# sct.net
KiCad netlist of a schematic drawn in EasyEDA
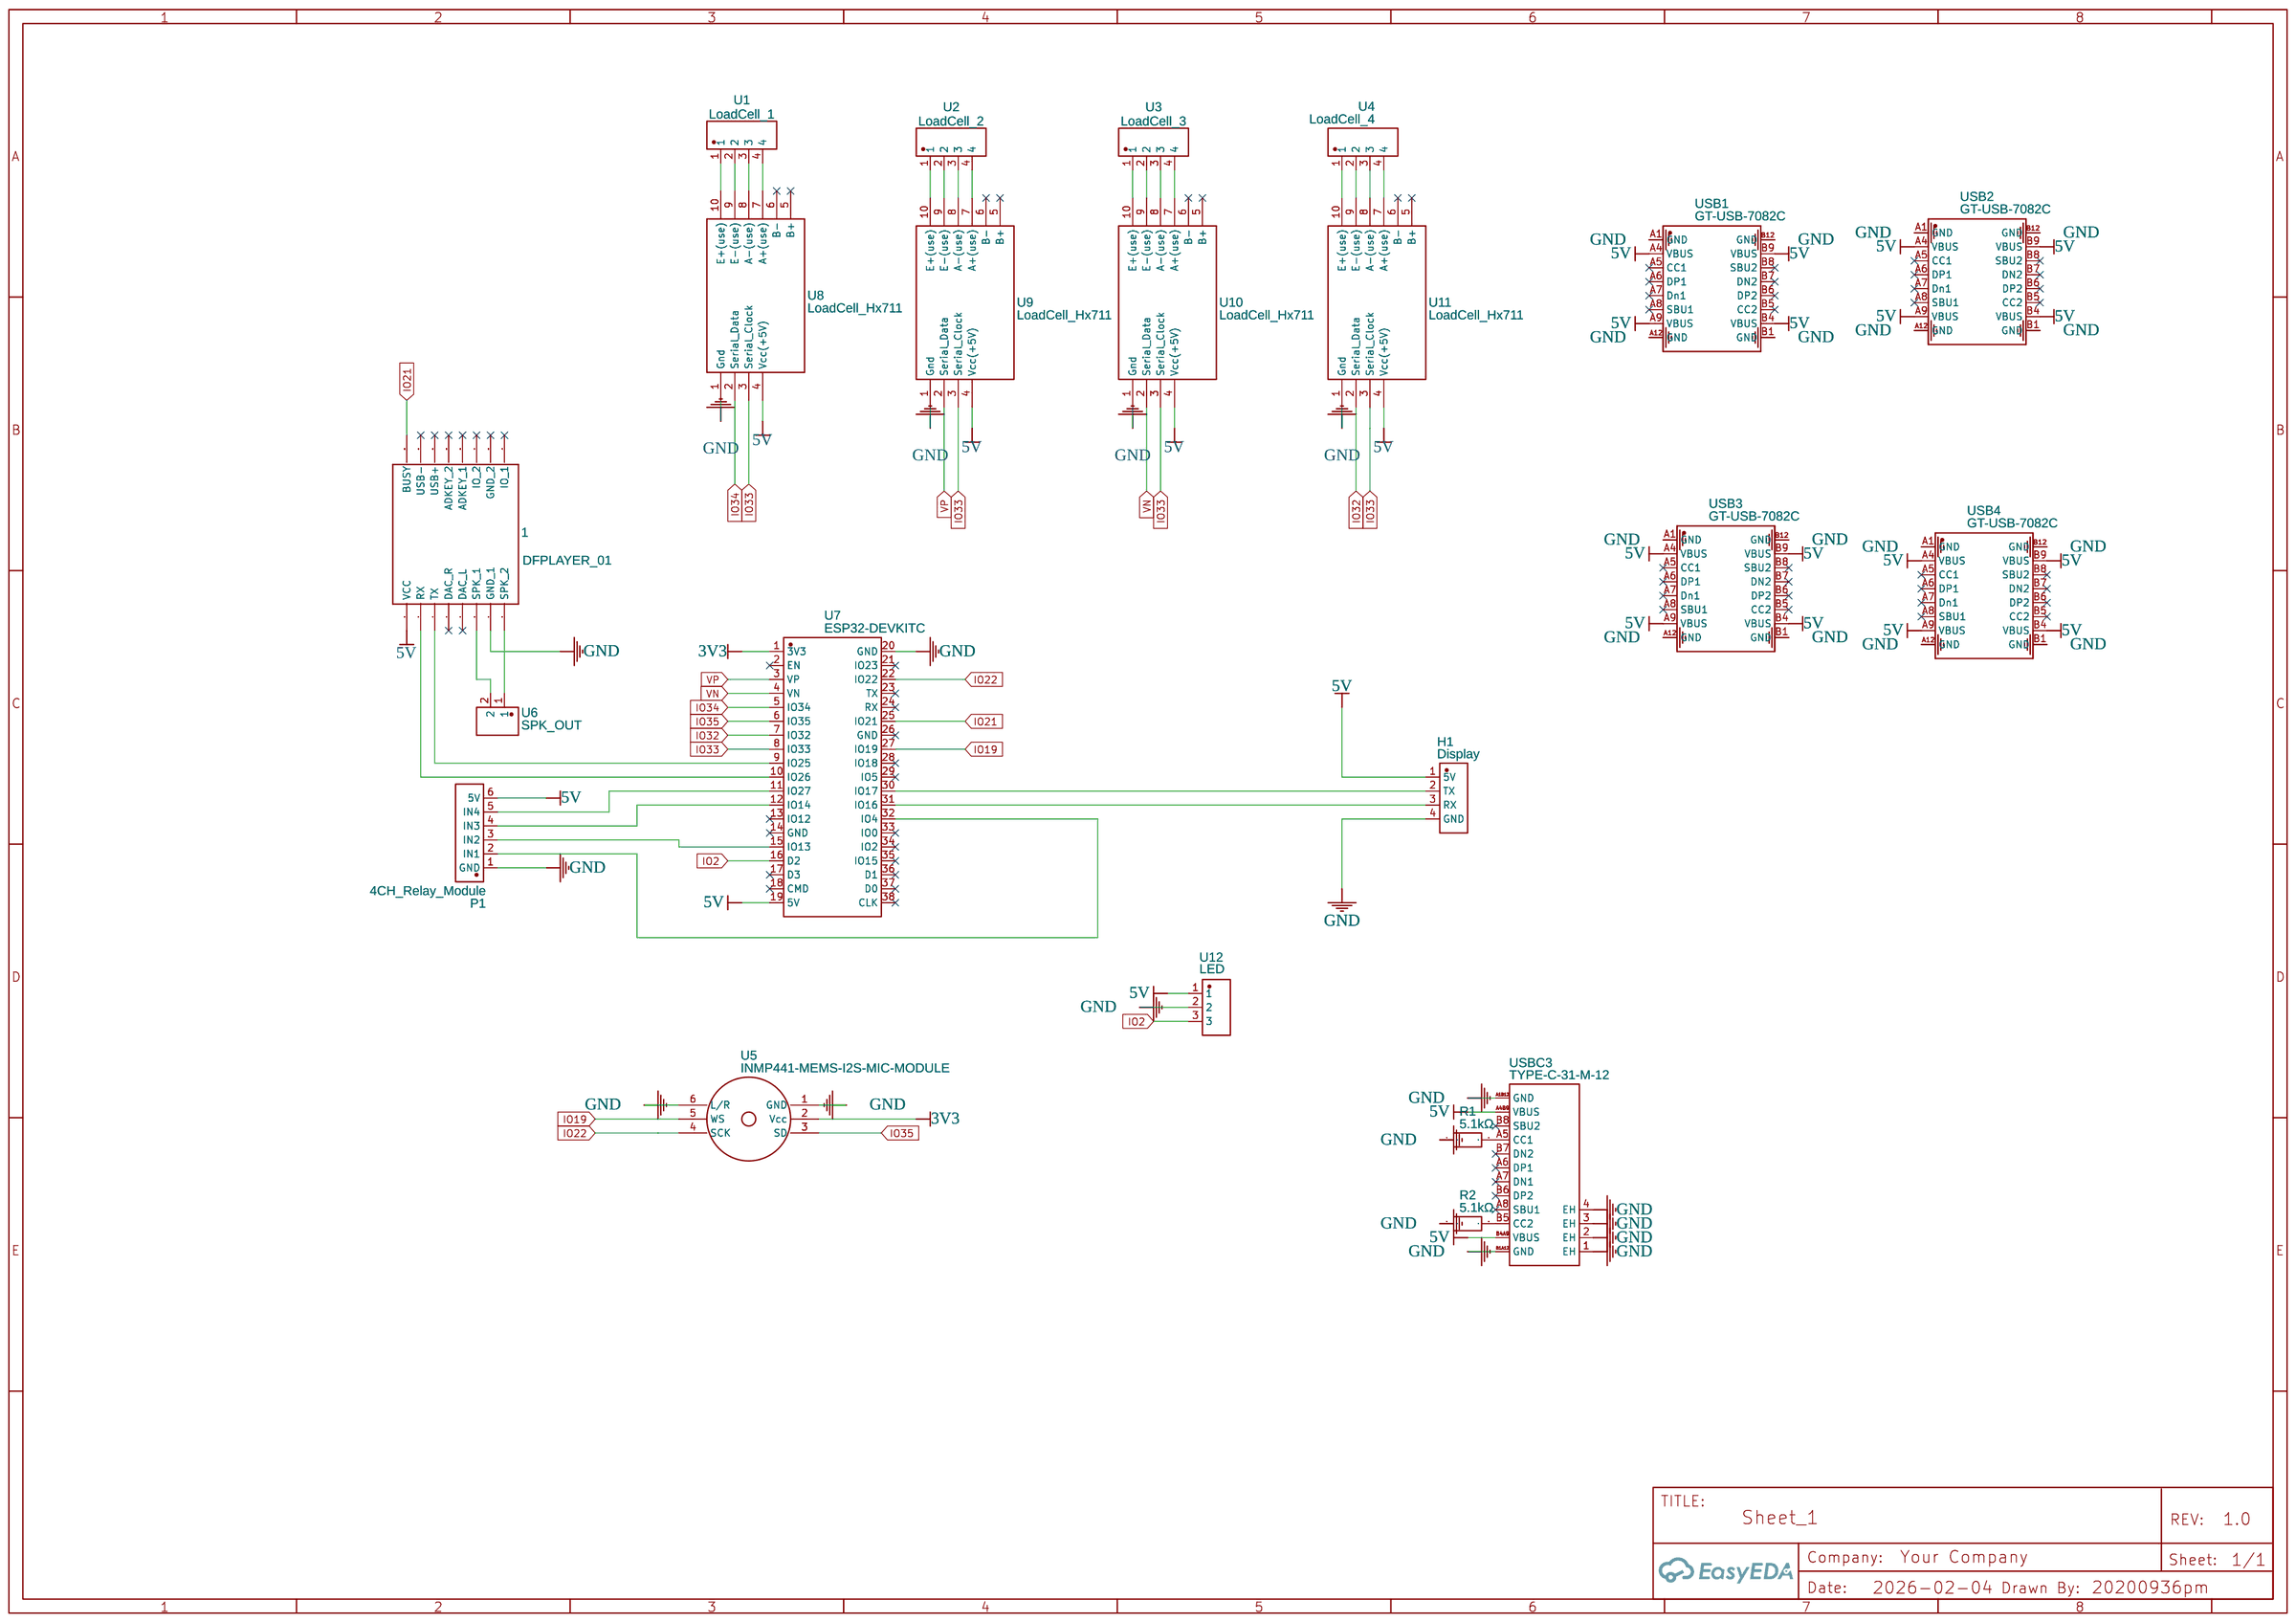
[diagram p0: schematic sheet]

(export (version "E")
  (design (tool "Eeschema 10.0.6"))
  (components
    (comp (ref "1") (value "DFPLAYER_01") (libsource (lib "") (part "DFPLAYER_01")))
    (comp (ref "H1")
      (value "Display")
      (fields (field (name "Manufacturer Part") "PZ254V-11-04P-A40") (field (name "Manufacturer") "XFCN(兴飞)"))
      (libsource (lib "") (part "PZ254V-11-04P-A40"))
    )
    (comp (ref "P1")
      (value "4CH_Relay_Module")
      (fields (field (name "Manufacturer Part") "2.54-1*6P母") (field (name "Manufacturer") "BOOMELE(博穆精密)"))
      (libsource (lib "") (part "Header-Female-2.54_1x6"))
    )
    (comp (ref "R1")
      (value "5.1kΩ")
      (fields
        (field (name "Manufacturer Part") "HoAR0603-1/10W-5.1KR-0.1%-TCR25")
        (field (name "Manufacturer") "Milliohm(毫欧)")
      )
      (libsource (lib "") (part "HOAR0603-1/10W-5.1KR-0.1%-TCR25"))
    )
    (comp (ref "R2")
      (value "5.1kΩ")
      (fields
        (field (name "Manufacturer Part") "HoAR0603-1/10W-5.1KR-0.1%-TCR25")
        (field (name "Manufacturer") "Milliohm(毫欧)")
      )
      (libsource (lib "") (part "HOAR0603-1/10W-5.1KR-0.1%-TCR25"))
    )
    (comp (ref "U1")
      (value "LoadCell_1")
      (fields (field (name "Manufacturer Part") "KF128-2.54-4P") (field (name "Manufacturer") "KEFA(科发)"))
      (libsource (lib "") (part "KF128-2.54-4P"))
    )
    (comp (ref "U2")
      (value "LoadCell_2")
      (fields (field (name "Manufacturer Part") "KF128-2.54-4P") (field (name "Manufacturer") "KEFA(科发)"))
      (libsource (lib "") (part "KF128-2.54-4P"))
    )
    (comp (ref "U3")
      (value "LoadCell_3")
      (fields (field (name "Manufacturer Part") "KF128-2.54-4P") (field (name "Manufacturer") "KEFA(科发)"))
      (libsource (lib "") (part "KF128-2.54-4P"))
    )
    (comp (ref "U4")
      (value "LoadCell_4")
      (fields (field (name "Manufacturer Part") "KF128-2.54-4P") (field (name "Manufacturer") "KEFA(科发)"))
      (libsource (lib "") (part "KF128-2.54-4P"))
    )
    (comp (ref "U5")
      (value "INMP441-MEMS-I2S-MIC-MODULE")
      (libsource (lib "") (part "INMP441-MEMS-I2S-MIC-MODULE"))
    )
    (comp (ref "U6")
      (value "SPK_OUT")
      (fields (field (name "Manufacturer Part") "KF301-5.0-2P") (field (name "Manufacturer") "KEFA(科发)"))
      (libsource (lib "") (part "KF301-5.0-2P"))
    )
    (comp (ref "U7")
      (value "ESP32-DEVKITC")
      (fields
        (field (name "Manufacturer Part") "ESP32-DevKitC")
        (field (name "Manufacturer") "ESPRESSIF(乐鑫)")
      )
      (libsource (lib "") (part "ESP32-DEVKITC"))
    )
    (comp (ref "U8") (value "LoadCell_Hx711") (libsource (lib "") (part "LoadCell_Hx711")))
    (comp (ref "U9") (value "LoadCell_Hx711") (libsource (lib "") (part "LoadCell_Hx711")))
    (comp (ref "U10") (value "LoadCell_Hx711") (libsource (lib "") (part "LoadCell_Hx711")))
    (comp (ref "U11") (value "LoadCell_Hx711") (libsource (lib "") (part "LoadCell_Hx711")))
    (comp (ref "U12")
      (value "LED")
      (fields
        (field (name "Manufacturer Part") "DW254R-11-03-85")
        (field (name "Manufacturer") "DEALON(德艺隆)")
      )
      (libsource (lib "") (part "DW254R-11-03-85"))
    )
    (comp (ref "USB1")
      (value "GT-USB-7082C")
      (fields (field (name "Manufacturer") "G-Switch(品赞)"))
      (libsource (lib "") (part "GT-USB-7082C"))
    )
    (comp (ref "USB2")
      (value "GT-USB-7082C")
      (fields (field (name "Manufacturer") "G-Switch(品赞)"))
      (libsource (lib "") (part "GT-USB-7082C"))
    )
    (comp (ref "USB3")
      (value "GT-USB-7082C")
      (fields (field (name "Manufacturer") "G-Switch(品赞)"))
      (libsource (lib "") (part "GT-USB-7082C"))
    )
    (comp (ref "USB4")
      (value "GT-USB-7082C")
      (fields (field (name "Manufacturer") "G-Switch(品赞)"))
      (libsource (lib "") (part "GT-USB-7082C"))
    )
    (comp (ref "USBC3")
      (value "TYPE-C-31-M-12")
      (fields (field (name "Manufacturer") "韩国韩荣"))
      (libsource (lib "") (part "TYPE-C-31-M-12"))
    )
  )
  (nets
    (net (code "1") (name "3V3") (class "Default")
      (node (ref "U5") (pin "2") (pinfunction "Vcc_2") (pintype "unspecified"))
      (node (ref "U7") (pin "1") (pinfunction "3V3_1") (pintype "unspecified"))
    )
    (net (code "2") (name "5V") (class "Default")
      (node (ref "1") (pin "VCC") (pinfunction "VCC_VCC") (pintype "bidirectional"))
      (node (ref "H1") (pin "1") (pinfunction "5V_1") (pintype "unspecified"))
      (node (ref "P1") (pin "6") (pinfunction "5V_6") (pintype "unspecified"))
      (node (ref "U10") (pin "4") (pinfunction "Vcc(+5V)_4") (pintype "unspecified"))
      (node (ref "U11") (pin "4") (pinfunction "Vcc(+5V)_4") (pintype "unspecified"))
      (node (ref "U12") (pin "1") (pinfunction "1_1") (pintype "unspecified"))
      (node (ref "U7") (pin "19") (pinfunction "5V_19") (pintype "unspecified"))
      (node (ref "U8") (pin "4") (pinfunction "Vcc(+5V)_4") (pintype "unspecified"))
      (node (ref "U9") (pin "4") (pinfunction "Vcc(+5V)_4") (pintype "unspecified"))
      (node (ref "USB1") (pin "A4") (pinfunction "VBUS_A4") (pintype "unspecified"))
      (node (ref "USB1") (pin "A9") (pinfunction "VBUS_A9") (pintype "unspecified"))
      (node (ref "USB1") (pin "B4") (pinfunction "VBUS_B4") (pintype "unspecified"))
      (node (ref "USB1") (pin "B9") (pinfunction "VBUS_B9") (pintype "unspecified"))
      (node (ref "USB2") (pin "A4") (pinfunction "VBUS_A4") (pintype "unspecified"))
      (node (ref "USB2") (pin "A9") (pinfunction "VBUS_A9") (pintype "unspecified"))
      (node (ref "USB2") (pin "B4") (pinfunction "VBUS_B4") (pintype "unspecified"))
      (node (ref "USB2") (pin "B9") (pinfunction "VBUS_B9") (pintype "unspecified"))
      (node (ref "USB3") (pin "A4") (pinfunction "VBUS_A4") (pintype "unspecified"))
      (node (ref "USB3") (pin "A9") (pinfunction "VBUS_A9") (pintype "unspecified"))
      (node (ref "USB3") (pin "B4") (pinfunction "VBUS_B4") (pintype "unspecified"))
      (node (ref "USB3") (pin "B9") (pinfunction "VBUS_B9") (pintype "unspecified"))
      (node (ref "USB4") (pin "A4") (pinfunction "VBUS_A4") (pintype "unspecified"))
      (node (ref "USB4") (pin "A9") (pinfunction "VBUS_A9") (pintype "unspecified"))
      (node (ref "USB4") (pin "B4") (pinfunction "VBUS_B4") (pintype "unspecified"))
      (node (ref "USB4") (pin "B9") (pinfunction "VBUS_B9") (pintype "unspecified"))
      (node (ref "USBC3") (pin "A4B9") (pinfunction "VBUS_A4B9") (pintype "unspecified"))
      (node (ref "USBC3") (pin "B4A9") (pinfunction "VBUS_B4A9") (pintype "unspecified"))
    )
    (net (code "3") (name "GND") (class "Default")
      (node (ref "1") (pin "GND_1") (pinfunction "GND_1_GND_1") (pintype "bidirectional"))
      (node (ref "H1") (pin "4") (pinfunction "GND_4") (pintype "unspecified"))
      (node (ref "P1") (pin "1") (pinfunction "GND_1") (pintype "unspecified"))
      (node (ref "R1") (pin "1") (pinfunction "1_1") (pintype "unspecified"))
      (node (ref "R2") (pin "1") (pinfunction "1_1") (pintype "unspecified"))
      (node (ref "U10") (pin "1") (pinfunction "Gnd_1") (pintype "unspecified"))
      (node (ref "U11") (pin "1") (pinfunction "Gnd_1") (pintype "unspecified"))
      (node (ref "U12") (pin "2") (pinfunction "2_2") (pintype "unspecified"))
      (node (ref "U5") (pin "1") (pinfunction "GND_1") (pintype "unspecified"))
      (node (ref "U5") (pin "6") (pinfunction "L/R_6") (pintype "unspecified"))
      (node (ref "U7") (pin "20") (pinfunction "GND_20") (pintype "unspecified"))
      (node (ref "U8") (pin "1") (pinfunction "Gnd_1") (pintype "unspecified"))
      (node (ref "U9") (pin "1") (pinfunction "Gnd_1") (pintype "unspecified"))
      (node (ref "USB1") (pin "A1") (pinfunction "GND_A1") (pintype "unspecified"))
      (node (ref "USB1") (pin "A12") (pinfunction "GND_A12") (pintype "unspecified"))
      (node (ref "USB1") (pin "B1") (pinfunction "GND_B1") (pintype "unspecified"))
      (node (ref "USB1") (pin "B12") (pinfunction "GND_B12") (pintype "unspecified"))
      (node (ref "USB2") (pin "A1") (pinfunction "GND_A1") (pintype "unspecified"))
      (node (ref "USB2") (pin "A12") (pinfunction "GND_A12") (pintype "unspecified"))
      (node (ref "USB2") (pin "B1") (pinfunction "GND_B1") (pintype "unspecified"))
      (node (ref "USB2") (pin "B12") (pinfunction "GND_B12") (pintype "unspecified"))
      (node (ref "USB3") (pin "A1") (pinfunction "GND_A1") (pintype "unspecified"))
      (node (ref "USB3") (pin "A12") (pinfunction "GND_A12") (pintype "unspecified"))
      (node (ref "USB3") (pin "B1") (pinfunction "GND_B1") (pintype "unspecified"))
      (node (ref "USB3") (pin "B12") (pinfunction "GND_B12") (pintype "unspecified"))
      (node (ref "USB4") (pin "A1") (pinfunction "GND_A1") (pintype "unspecified"))
      (node (ref "USB4") (pin "A12") (pinfunction "GND_A12") (pintype "unspecified"))
      (node (ref "USB4") (pin "B1") (pinfunction "GND_B1") (pintype "unspecified"))
      (node (ref "USB4") (pin "B12") (pinfunction "GND_B12") (pintype "unspecified"))
      (node (ref "USBC3") (pin "1") (pinfunction "EH_1") (pintype "unspecified"))
      (node (ref "USBC3") (pin "2") (pinfunction "EH_2") (pintype "unspecified"))
      (node (ref "USBC3") (pin "3") (pinfunction "EH_3") (pintype "unspecified"))
      (node (ref "USBC3") (pin "4") (pinfunction "EH_4") (pintype "unspecified"))
      (node (ref "USBC3") (pin "A1B12") (pinfunction "GND_A1B12") (pintype "unspecified"))
      (node (ref "USBC3") (pin "B1A12") (pinfunction "GND_B1A12") (pintype "unspecified"))
    )
    (net (code "4") (name "IO2") (class "Default")
      (node (ref "U12") (pin "3") (pinfunction "3_3") (pintype "unspecified"))
      (node (ref "U7") (pin "16") (pinfunction "D2_16") (pintype "unspecified"))
    )
    (net (code "5") (name "IO19") (class "Default")
      (node (ref "U5") (pin "5") (pinfunction "WS_5") (pintype "unspecified"))
      (node (ref "U7") (pin "27") (pinfunction "IO19_27") (pintype "unspecified"))
    )
    (net (code "6") (name "IO21") (class "Default")
      (node (ref "1") (pin "BUSY") (pinfunction "BUSY_BUSY") (pintype "bidirectional"))
      (node (ref "U7") (pin "25") (pinfunction "IO21_25") (pintype "unspecified"))
    )
    (net (code "7") (name "IO22") (class "Default")
      (node (ref "U5") (pin "4") (pinfunction "SCK_4") (pintype "unspecified"))
      (node (ref "U7") (pin "22") (pinfunction "IO22_22") (pintype "unspecified"))
    )
    (net (code "8") (name "IO32") (class "Default")
      (node (ref "U11") (pin "2") (pinfunction "Serial_Data_2") (pintype "unspecified"))
      (node (ref "U7") (pin "7") (pinfunction "IO32_7") (pintype "unspecified"))
    )
    (net (code "9") (name "IO33") (class "Default")
      (node (ref "U10") (pin "3") (pinfunction "Serial_Clock_3") (pintype "unspecified"))
      (node (ref "U11") (pin "3") (pinfunction "Serial_Clock_3") (pintype "unspecified"))
      (node (ref "U7") (pin "8") (pinfunction "IO33_8") (pintype "unspecified"))
      (node (ref "U8") (pin "3") (pinfunction "Serial_Clock_3") (pintype "unspecified"))
      (node (ref "U9") (pin "3") (pinfunction "Serial_Clock_3") (pintype "unspecified"))
    )
    (net (code "10") (name "IO34") (class "Default")
      (node (ref "U7") (pin "5") (pinfunction "IO34_5") (pintype "unspecified"))
      (node (ref "U8") (pin "2") (pinfunction "Serial_Data_2") (pintype "unspecified"))
    )
    (net (code "11") (name "IO35") (class "Default")
      (node (ref "U5") (pin "3") (pinfunction "SD_3") (pintype "unspecified"))
      (node (ref "U7") (pin "6") (pinfunction "IO35_6") (pintype "unspecified"))
    )
    (net (code "12") (name "Net-(1-SPK_1)") (class "Default")
      (node (ref "1") (pin "SPK1") (pinfunction "SPK_1_SPK1") (pintype "bidirectional"))
      (node (ref "U6") (pin "2") (pinfunction "2_2") (pintype "unspecified"))
    )
    (net (code "13") (name "Net-(1-SPK_2)") (class "Default")
      (node (ref "1") (pin "SPK2") (pinfunction "SPK_2_SPK2") (pintype "bidirectional"))
      (node (ref "U6") (pin "1") (pinfunction "1_1") (pintype "unspecified"))
    )
    (net (code "14") (name "Net-(H1-RX)") (class "Default")
      (node (ref "H1") (pin "3") (pinfunction "RX_3") (pintype "unspecified"))
      (node (ref "U7") (pin "31") (pinfunction "IO16_31") (pintype "unspecified"))
    )
    (net (code "15") (name "Net-(H1-TX)") (class "Default")
      (node (ref "H1") (pin "2") (pinfunction "TX_2") (pintype "unspecified"))
      (node (ref "U7") (pin "30") (pinfunction "IO17_30") (pintype "unspecified"))
    )
    (net (code "16") (name "Net-(P1-IN1)") (class "Default")
      (node (ref "P1") (pin "2") (pinfunction "IN1_2") (pintype "unspecified"))
      (node (ref "U7") (pin "32") (pinfunction "IO4_32") (pintype "unspecified"))
    )
    (net (code "17") (name "Net-(P1-IN2)") (class "Default")
      (node (ref "P1") (pin "3") (pinfunction "IN2_3") (pintype "unspecified"))
      (node (ref "U7") (pin "15") (pinfunction "IO13_15") (pintype "unspecified"))
    )
    (net (code "18") (name "Net-(P1-IN3)") (class "Default")
      (node (ref "P1") (pin "4") (pinfunction "IN3_4") (pintype "unspecified"))
      (node (ref "U7") (pin "12") (pinfunction "IO14_12") (pintype "unspecified"))
    )
    (net (code "19") (name "Net-(P1-IN4)") (class "Default")
      (node (ref "P1") (pin "5") (pinfunction "IN4_5") (pintype "unspecified"))
      (node (ref "U7") (pin "11") (pinfunction "IO27_11") (pintype "unspecified"))
    )
    (net (code "20") (name "Net-(U7-IO25)") (class "Default")
      (node (ref "1") (pin "TX") (pinfunction "TX_TX") (pintype "bidirectional"))
      (node (ref "U7") (pin "9") (pinfunction "IO25_9") (pintype "unspecified"))
    )
    (net (code "21") (name "Net-(U7-IO26)") (class "Default")
      (node (ref "1") (pin "RX") (pinfunction "RX_RX") (pintype "bidirectional"))
      (node (ref "U7") (pin "10") (pinfunction "IO26_10") (pintype "unspecified"))
    )
    (net (code "22") (name "Net-(U8-A+(use))") (class "Default")
      (node (ref "U1") (pin "4") (pinfunction "4_4") (pintype "unspecified"))
      (node (ref "U8") (pin "7") (pinfunction "A+(use)_7") (pintype "unspecified"))
    )
    (net (code "23") (name "Net-(U8-A-(use))") (class "Default")
      (node (ref "U1") (pin "3") (pinfunction "3_3") (pintype "unspecified"))
      (node (ref "U8") (pin "8") (pinfunction "A-(use)_8") (pintype "unspecified"))
    )
    (net (code "24") (name "Net-(U8-E+(use))") (class "Default")
      (node (ref "U1") (pin "1") (pinfunction "1_1") (pintype "unspecified"))
      (node (ref "U8") (pin "10") (pinfunction "E+(use)_10") (pintype "unspecified"))
    )
    (net (code "25") (name "Net-(U8-E-(use))") (class "Default")
      (node (ref "U1") (pin "2") (pinfunction "2_2") (pintype "unspecified"))
      (node (ref "U8") (pin "9") (pinfunction "E-(use)_9") (pintype "unspecified"))
    )
    (net (code "26") (name "Net-(U9-A+(use))") (class "Default")
      (node (ref "U2") (pin "4") (pinfunction "4_4") (pintype "unspecified"))
      (node (ref "U9") (pin "7") (pinfunction "A+(use)_7") (pintype "unspecified"))
    )
    (net (code "27") (name "Net-(U9-A-(use))") (class "Default")
      (node (ref "U2") (pin "3") (pinfunction "3_3") (pintype "unspecified"))
      (node (ref "U9") (pin "8") (pinfunction "A-(use)_8") (pintype "unspecified"))
    )
    (net (code "28") (name "Net-(U9-E+(use))") (class "Default")
      (node (ref "U2") (pin "1") (pinfunction "1_1") (pintype "unspecified"))
      (node (ref "U9") (pin "10") (pinfunction "E+(use)_10") (pintype "unspecified"))
    )
    (net (code "29") (name "Net-(U9-E-(use))") (class "Default")
      (node (ref "U2") (pin "2") (pinfunction "2_2") (pintype "unspecified"))
      (node (ref "U9") (pin "9") (pinfunction "E-(use)_9") (pintype "unspecified"))
    )
    (net (code "30") (name "Net-(U10-A+(use))") (class "Default")
      (node (ref "U10") (pin "7") (pinfunction "A+(use)_7") (pintype "unspecified"))
      (node (ref "U3") (pin "4") (pinfunction "4_4") (pintype "unspecified"))
    )
    (net (code "31") (name "Net-(U10-A-(use))") (class "Default")
      (node (ref "U10") (pin "8") (pinfunction "A-(use)_8") (pintype "unspecified"))
      (node (ref "U3") (pin "3") (pinfunction "3_3") (pintype "unspecified"))
    )
    (net (code "32") (name "Net-(U10-E+(use))") (class "Default")
      (node (ref "U10") (pin "10") (pinfunction "E+(use)_10") (pintype "unspecified"))
      (node (ref "U3") (pin "1") (pinfunction "1_1") (pintype "unspecified"))
    )
    (net (code "33") (name "Net-(U10-E-(use))") (class "Default")
      (node (ref "U10") (pin "9") (pinfunction "E-(use)_9") (pintype "unspecified"))
      (node (ref "U3") (pin "2") (pinfunction "2_2") (pintype "unspecified"))
    )
    (net (code "34") (name "Net-(U11-A+(use))") (class "Default")
      (node (ref "U11") (pin "7") (pinfunction "A+(use)_7") (pintype "unspecified"))
      (node (ref "U4") (pin "4") (pinfunction "4_4") (pintype "unspecified"))
    )
    (net (code "35") (name "Net-(U11-A-(use))") (class "Default")
      (node (ref "U11") (pin "8") (pinfunction "A-(use)_8") (pintype "unspecified"))
      (node (ref "U4") (pin "3") (pinfunction "3_3") (pintype "unspecified"))
    )
    (net (code "36") (name "Net-(U11-E+(use))") (class "Default")
      (node (ref "U11") (pin "10") (pinfunction "E+(use)_10") (pintype "unspecified"))
      (node (ref "U4") (pin "1") (pinfunction "1_1") (pintype "unspecified"))
    )
    (net (code "37") (name "Net-(U11-E-(use))") (class "Default")
      (node (ref "U11") (pin "9") (pinfunction "E-(use)_9") (pintype "unspecified"))
      (node (ref "U4") (pin "2") (pinfunction "2_2") (pintype "unspecified"))
    )
    (net (code "38") (name "Net-(USBC3-CC1)") (class "Default")
      (node (ref "R1") (pin "2") (pinfunction "2_2") (pintype "unspecified"))
      (node (ref "USBC3") (pin "A5") (pinfunction "CC1_A5") (pintype "unspecified"))
    )
    (net (code "39") (name "Net-(USBC3-CC2)") (class "Default")
      (node (ref "R2") (pin "2") (pinfunction "2_2") (pintype "unspecified"))
      (node (ref "USBC3") (pin "B5") (pinfunction "CC2_B5") (pintype "unspecified"))
    )
    (net (code "40") (name "VN") (class "Default")
      (node (ref "U10") (pin "2") (pinfunction "Serial_Data_2") (pintype "unspecified"))
      (node (ref "U7") (pin "4") (pinfunction "VN_4") (pintype "unspecified"))
    )
    (net (code "41") (name "VP") (class "Default")
      (node (ref "U7") (pin "3") (pinfunction "VP_3") (pintype "unspecified"))
      (node (ref "U9") (pin "2") (pinfunction "Serial_Data_2") (pintype "unspecified"))
    )
    (net (code "42") (name "unconnected-(1-ADKEY_1-PadADKEY1)") (class "Default")
      (node (ref "1") (pin "ADKEY1") (pinfunction "ADKEY_1_ADKEY1") (pintype "bidirectional+no_connect"))
    )
    (net (code "43") (name "unconnected-(1-ADKEY_2-PadADKEY2)") (class "Default")
      (node (ref "1") (pin "ADKEY2") (pinfunction "ADKEY_2_ADKEY2") (pintype "bidirectional+no_connect"))
    )
    (net (code "44") (name "unconnected-(1-IO_1-PadIO1)") (class "Default")
      (node (ref "1") (pin "IO1") (pinfunction "IO_1_IO1") (pintype "bidirectional+no_connect"))
    )
    (net (code "45") (name "unconnected-(1-IO_2-PadIO2)") (class "Default")
      (node (ref "1") (pin "IO2") (pinfunction "IO_2_IO2") (pintype "bidirectional+no_connect"))
    )
    (net (code "46") (name "unconnected-(1-PadDAC_L)") (class "Default")
      (node (ref "1") (pin "DAC_L") (pinfunction "DAC_L_DAC_L") (pintype "bidirectional+no_connect"))
    )
    (net (code "47") (name "unconnected-(1-PadDAC_R)") (class "Default")
      (node (ref "1") (pin "DAC_R") (pinfunction "DAC_R_DAC_R") (pintype "bidirectional+no_connect"))
    )
    (net (code "48") (name "unconnected-(1-PadGND_2)") (class "Default")
      (node (ref "1") (pin "GND_2") (pinfunction "GND_2_GND_2") (pintype "bidirectional+no_connect"))
    )
    (net (code "49") (name "unconnected-(1-PadUSB+)") (class "Default")
      (node (ref "1") (pin "USB+") (pinfunction "USB+_USB+") (pintype "bidirectional+no_connect"))
    )
    (net (code "50") (name "unconnected-(1-PadUSB-)") (class "Default")
      (node (ref "1") (pin "USB-") (pinfunction "USB-_USB-") (pintype "bidirectional+no_connect"))
    )
    (net (code "51") (name "unconnected-(U7-CLK-Pad38)") (class "Default")
      (node (ref "U7") (pin "38") (pinfunction "CLK_38") (pintype "unspecified+no_connect"))
    )
    (net (code "52") (name "unconnected-(U7-CMD-Pad18)") (class "Default")
      (node (ref "U7") (pin "18") (pinfunction "CMD_18") (pintype "unspecified+no_connect"))
    )
    (net (code "53") (name "unconnected-(U7-D0-Pad37)") (class "Default")
      (node (ref "U7") (pin "37") (pinfunction "D0_37") (pintype "unspecified+no_connect"))
    )
    (net (code "54") (name "unconnected-(U7-D1-Pad36)") (class "Default")
      (node (ref "U7") (pin "36") (pinfunction "D1_36") (pintype "unspecified+no_connect"))
    )
    (net (code "55") (name "unconnected-(U7-D3-Pad17)") (class "Default")
      (node (ref "U7") (pin "17") (pinfunction "D3_17") (pintype "unspecified+no_connect"))
    )
    (net (code "56") (name "unconnected-(U7-EN-Pad2)") (class "Default")
      (node (ref "U7") (pin "2") (pinfunction "EN_2") (pintype "unspecified+no_connect"))
    )
    (net (code "57") (name "unconnected-(U7-GND-Pad14)") (class "Default")
      (node (ref "U7") (pin "14") (pinfunction "GND_14") (pintype "unspecified+no_connect"))
    )
    (net (code "58") (name "unconnected-(U7-GND-Pad26)") (class "Default")
      (node (ref "U7") (pin "26") (pinfunction "GND_26") (pintype "unspecified+no_connect"))
    )
    (net (code "59") (name "unconnected-(U7-IO0-Pad33)") (class "Default")
      (node (ref "U7") (pin "33") (pinfunction "IO0_33") (pintype "unspecified+no_connect"))
    )
    (net (code "60") (name "unconnected-(U7-IO2-Pad34)") (class "Default")
      (node (ref "U7") (pin "34") (pinfunction "IO2_34") (pintype "unspecified+no_connect"))
    )
    (net (code "61") (name "unconnected-(U7-IO5-Pad29)") (class "Default")
      (node (ref "U7") (pin "29") (pinfunction "IO5_29") (pintype "unspecified+no_connect"))
    )
    (net (code "62") (name "unconnected-(U7-IO12-Pad13)") (class "Default")
      (node (ref "U7") (pin "13") (pinfunction "IO12_13") (pintype "unspecified+no_connect"))
    )
    (net (code "63") (name "unconnected-(U7-IO15-Pad35)") (class "Default")
      (node (ref "U7") (pin "35") (pinfunction "IO15_35") (pintype "unspecified+no_connect"))
    )
    (net (code "64") (name "unconnected-(U7-IO18-Pad28)") (class "Default")
      (node (ref "U7") (pin "28") (pinfunction "IO18_28") (pintype "unspecified+no_connect"))
    )
    (net (code "65") (name "unconnected-(U7-IO23-Pad21)") (class "Default")
      (node (ref "U7") (pin "21") (pinfunction "IO23_21") (pintype "unspecified+no_connect"))
    )
    (net (code "66") (name "unconnected-(U7-RX-Pad24)") (class "Default")
      (node (ref "U7") (pin "24") (pinfunction "RX_24") (pintype "unspecified+no_connect"))
    )
    (net (code "67") (name "unconnected-(U7-TX-Pad23)") (class "Default")
      (node (ref "U7") (pin "23") (pinfunction "TX_23") (pintype "unspecified+no_connect"))
    )
    (net (code "68") (name "unconnected-(U8-B+-Pad5)") (class "Default")
      (node (ref "U8") (pin "5") (pinfunction "B+_5") (pintype "unspecified+no_connect"))
    )
    (net (code "69") (name "unconnected-(U8-B--Pad6)") (class "Default")
      (node (ref "U8") (pin "6") (pinfunction "B-_6") (pintype "unspecified+no_connect"))
    )
    (net (code "70") (name "unconnected-(U9-B+-Pad5)") (class "Default")
      (node (ref "U9") (pin "5") (pinfunction "B+_5") (pintype "unspecified+no_connect"))
    )
    (net (code "71") (name "unconnected-(U9-B--Pad6)") (class "Default")
      (node (ref "U9") (pin "6") (pinfunction "B-_6") (pintype "unspecified+no_connect"))
    )
    (net (code "72") (name "unconnected-(U10-B+-Pad5)") (class "Default")
      (node (ref "U10") (pin "5") (pinfunction "B+_5") (pintype "unspecified+no_connect"))
    )
    (net (code "73") (name "unconnected-(U10-B--Pad6)") (class "Default")
      (node (ref "U10") (pin "6") (pinfunction "B-_6") (pintype "unspecified+no_connect"))
    )
    (net (code "74") (name "unconnected-(U11-B+-Pad5)") (class "Default")
      (node (ref "U11") (pin "5") (pinfunction "B+_5") (pintype "unspecified+no_connect"))
    )
    (net (code "75") (name "unconnected-(U11-B--Pad6)") (class "Default")
      (node (ref "U11") (pin "6") (pinfunction "B-_6") (pintype "unspecified+no_connect"))
    )
    (net (code "76") (name "unconnected-(USB1-CC1-PadA5)") (class "Default")
      (node (ref "USB1") (pin "A5") (pinfunction "CC1_A5") (pintype "unspecified+no_connect"))
    )
    (net (code "77") (name "unconnected-(USB1-CC2-PadB5)") (class "Default")
      (node (ref "USB1") (pin "B5") (pinfunction "CC2_B5") (pintype "unspecified+no_connect"))
    )
    (net (code "78") (name "unconnected-(USB1-DN2-PadB7)") (class "Default")
      (node (ref "USB1") (pin "B7") (pinfunction "DN2_B7") (pintype "unspecified+no_connect"))
    )
    (net (code "79") (name "unconnected-(USB1-DP1-PadA6)") (class "Default")
      (node (ref "USB1") (pin "A6") (pinfunction "DP1_A6") (pintype "unspecified+no_connect"))
    )
    (net (code "80") (name "unconnected-(USB1-DP2-PadB6)") (class "Default")
      (node (ref "USB1") (pin "B6") (pinfunction "DP2_B6") (pintype "unspecified+no_connect"))
    )
    (net (code "81") (name "unconnected-(USB1-Dn1-PadA7)") (class "Default")
      (node (ref "USB1") (pin "A7") (pinfunction "Dn1_A7") (pintype "unspecified+no_connect"))
    )
    (net (code "82") (name "unconnected-(USB1-SBU1-PadA8)") (class "Default")
      (node (ref "USB1") (pin "A8") (pinfunction "SBU1_A8") (pintype "unspecified+no_connect"))
    )
    (net (code "83") (name "unconnected-(USB1-SBU2-PadB8)") (class "Default")
      (node (ref "USB1") (pin "B8") (pinfunction "SBU2_B8") (pintype "unspecified+no_connect"))
    )
    (net (code "84") (name "unconnected-(USB2-CC1-PadA5)") (class "Default")
      (node (ref "USB2") (pin "A5") (pinfunction "CC1_A5") (pintype "unspecified+no_connect"))
    )
    (net (code "85") (name "unconnected-(USB2-CC2-PadB5)") (class "Default")
      (node (ref "USB2") (pin "B5") (pinfunction "CC2_B5") (pintype "unspecified+no_connect"))
    )
    (net (code "86") (name "unconnected-(USB2-DN2-PadB7)") (class "Default")
      (node (ref "USB2") (pin "B7") (pinfunction "DN2_B7") (pintype "unspecified+no_connect"))
    )
    (net (code "87") (name "unconnected-(USB2-DP1-PadA6)") (class "Default")
      (node (ref "USB2") (pin "A6") (pinfunction "DP1_A6") (pintype "unspecified+no_connect"))
    )
    (net (code "88") (name "unconnected-(USB2-DP2-PadB6)") (class "Default")
      (node (ref "USB2") (pin "B6") (pinfunction "DP2_B6") (pintype "unspecified+no_connect"))
    )
    (net (code "89") (name "unconnected-(USB2-Dn1-PadA7)") (class "Default")
      (node (ref "USB2") (pin "A7") (pinfunction "Dn1_A7") (pintype "unspecified+no_connect"))
    )
    (net (code "90") (name "unconnected-(USB2-SBU1-PadA8)") (class "Default")
      (node (ref "USB2") (pin "A8") (pinfunction "SBU1_A8") (pintype "unspecified+no_connect"))
    )
    (net (code "91") (name "unconnected-(USB2-SBU2-PadB8)") (class "Default")
      (node (ref "USB2") (pin "B8") (pinfunction "SBU2_B8") (pintype "unspecified+no_connect"))
    )
    (net (code "92") (name "unconnected-(USB3-CC1-PadA5)") (class "Default")
      (node (ref "USB3") (pin "A5") (pinfunction "CC1_A5") (pintype "unspecified+no_connect"))
    )
    (net (code "93") (name "unconnected-(USB3-CC2-PadB5)") (class "Default")
      (node (ref "USB3") (pin "B5") (pinfunction "CC2_B5") (pintype "unspecified+no_connect"))
    )
    (net (code "94") (name "unconnected-(USB3-DN2-PadB7)") (class "Default")
      (node (ref "USB3") (pin "B7") (pinfunction "DN2_B7") (pintype "unspecified+no_connect"))
    )
    (net (code "95") (name "unconnected-(USB3-DP1-PadA6)") (class "Default")
      (node (ref "USB3") (pin "A6") (pinfunction "DP1_A6") (pintype "unspecified+no_connect"))
    )
    (net (code "96") (name "unconnected-(USB3-DP2-PadB6)") (class "Default")
      (node (ref "USB3") (pin "B6") (pinfunction "DP2_B6") (pintype "unspecified+no_connect"))
    )
    (net (code "97") (name "unconnected-(USB3-Dn1-PadA7)") (class "Default")
      (node (ref "USB3") (pin "A7") (pinfunction "Dn1_A7") (pintype "unspecified+no_connect"))
    )
    (net (code "98") (name "unconnected-(USB3-SBU1-PadA8)") (class "Default")
      (node (ref "USB3") (pin "A8") (pinfunction "SBU1_A8") (pintype "unspecified+no_connect"))
    )
    (net (code "99") (name "unconnected-(USB3-SBU2-PadB8)") (class "Default")
      (node (ref "USB3") (pin "B8") (pinfunction "SBU2_B8") (pintype "unspecified+no_connect"))
    )
    (net (code "100") (name "unconnected-(USB4-CC1-PadA5)") (class "Default")
      (node (ref "USB4") (pin "A5") (pinfunction "CC1_A5") (pintype "unspecified+no_connect"))
    )
    (net (code "101") (name "unconnected-(USB4-CC2-PadB5)") (class "Default")
      (node (ref "USB4") (pin "B5") (pinfunction "CC2_B5") (pintype "unspecified+no_connect"))
    )
    (net (code "102") (name "unconnected-(USB4-DN2-PadB7)") (class "Default")
      (node (ref "USB4") (pin "B7") (pinfunction "DN2_B7") (pintype "unspecified+no_connect"))
    )
    (net (code "103") (name "unconnected-(USB4-DP1-PadA6)") (class "Default")
      (node (ref "USB4") (pin "A6") (pinfunction "DP1_A6") (pintype "unspecified+no_connect"))
    )
    (net (code "104") (name "unconnected-(USB4-DP2-PadB6)") (class "Default")
      (node (ref "USB4") (pin "B6") (pinfunction "DP2_B6") (pintype "unspecified+no_connect"))
    )
    (net (code "105") (name "unconnected-(USB4-Dn1-PadA7)") (class "Default")
      (node (ref "USB4") (pin "A7") (pinfunction "Dn1_A7") (pintype "unspecified+no_connect"))
    )
    (net (code "106") (name "unconnected-(USB4-SBU1-PadA8)") (class "Default")
      (node (ref "USB4") (pin "A8") (pinfunction "SBU1_A8") (pintype "unspecified+no_connect"))
    )
    (net (code "107") (name "unconnected-(USB4-SBU2-PadB8)") (class "Default")
      (node (ref "USB4") (pin "B8") (pinfunction "SBU2_B8") (pintype "unspecified+no_connect"))
    )
    (net (code "108") (name "unconnected-(USBC3-DN1-PadA7)") (class "Default")
      (node (ref "USBC3") (pin "A7") (pinfunction "DN1_A7") (pintype "unspecified+no_connect"))
    )
    (net (code "109") (name "unconnected-(USBC3-DN2-PadB7)") (class "Default")
      (node (ref "USBC3") (pin "B7") (pinfunction "DN2_B7") (pintype "unspecified+no_connect"))
    )
    (net (code "110") (name "unconnected-(USBC3-DP1-PadA6)") (class "Default")
      (node (ref "USBC3") (pin "A6") (pinfunction "DP1_A6") (pintype "unspecified+no_connect"))
    )
    (net (code "111") (name "unconnected-(USBC3-DP2-PadB6)") (class "Default")
      (node (ref "USBC3") (pin "B6") (pinfunction "DP2_B6") (pintype "unspecified+no_connect"))
    )
    (net (code "112") (name "unconnected-(USBC3-SBU1-PadA8)") (class "Default")
      (node (ref "USBC3") (pin "A8") (pinfunction "SBU1_A8") (pintype "unspecified+no_connect"))
    )
    (net (code "113") (name "unconnected-(USBC3-SBU2-PadB8)") (class "Default")
      (node (ref "USBC3") (pin "B8") (pinfunction "SBU2_B8") (pintype "unspecified+no_connect"))
    )
  )
)
